# BMS029B_Monitor.net
KiCad netlist of a schematic drawn in Altium Designer
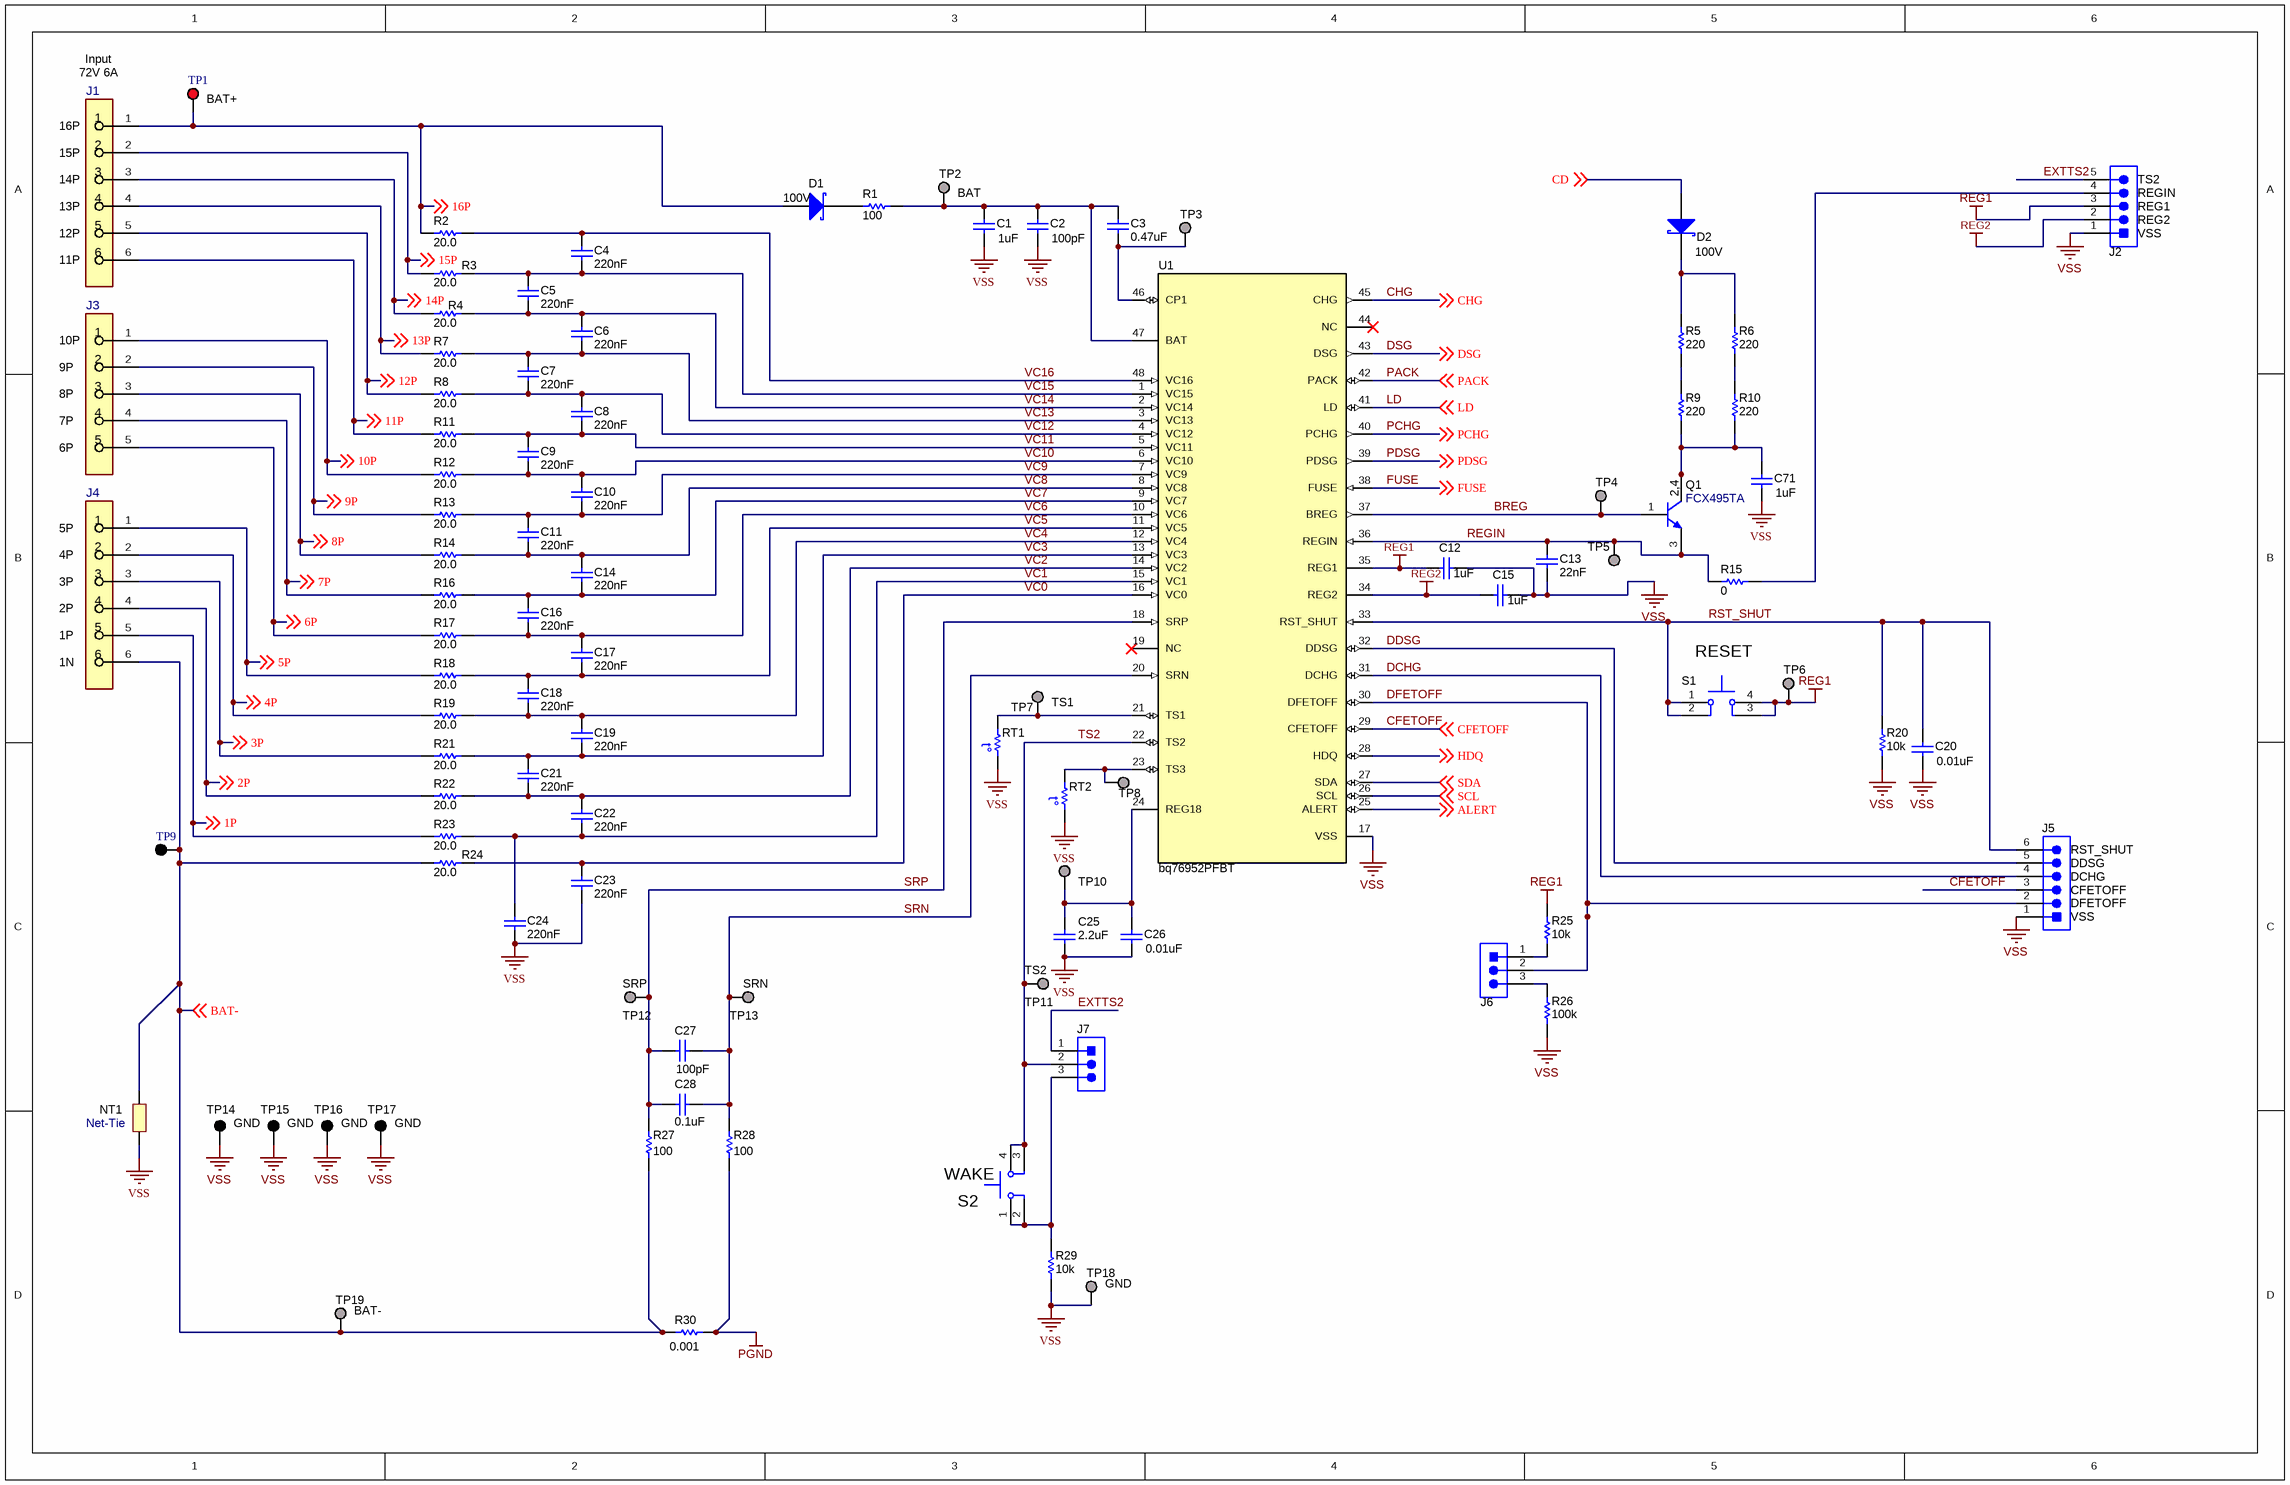
[diagram p0: BMS029B_Monitor.SchDoc]

(export (version "E")
  (design (tool "Eeschema 10.0.6"))
  (components
    (comp (ref "C1")
      (value "C3216X7R2A105K160AA")
      (footprint "1206_180")
      (description "CAP, CERM, 1 uF, 100 V, +/- 10%, X7R, 1206")
      (fields
        (field (name "MANUFACTURER") "TDK")
        (field (name "VALUEDISPLAYED") "1uF")
        (field (name "PUBLISHER") "Texas Instruments")
      )
      (libsource (lib "Altium Vault - TI") (part "Capacitor"))
    )
    (comp (ref "C2")
      (value "GCM1885C2A101JA16D")
      (footprint "0603")
      (description "CAP, CERM, 100 pF, 100 V, +/- 5%, C0G/NP0, AEC-Q200 Grade 1, 0603")
      (fields
        (field (name "MANUFACTURER") "MuRata")
        (field (name "VALUEDISPLAYED") "100pF")
        (field (name "PUBLISHER") "Texas Instruments")
      )
      (libsource (lib "Altium Vault - TI") (part "Capacitor"))
    )
    (comp (ref "C3")
      (value "GCM219R71E474KA55D")
      (footprint "0805_HV")
      (description "CAP, CERM, 0.47 uF, 25 V, +/- 10%, X7R, AEC-Q200 Grade 1, 0805")
      (fields
        (field (name "MANUFACTURER") "MuRata")
        (field (name "VALUEDISPLAYED") "0.47uF")
        (field (name "PUBLISHER") "Texas Instruments")
      )
      (libsource (lib "Altium Vault - TI") (part "Capacitor"))
    )
    (comp (ref "C4")
      (value "C1608X7R1H224K080AB")
      (footprint "0603S")
      (description "CAP, CERM, 0.22 uF, 50 V, +/- 10%, X7R, 0603")
      (fields
        (field (name "MANUFACTURER") "TDK")
        (field (name "CAP_F") "220nF")
        (field (name "PUBLISHER") "Texas Instruments")
      )
      (libsource (lib "Altium Vault - TI") (part "Capacitor"))
    )
    (comp (ref "C5")
      (value "C1608X7R1H224K080AB")
      (footprint "0603S")
      (description "CAP, CERM, 0.22 uF, 50 V, +/- 10%, X7R, 0603")
      (fields
        (field (name "MANUFACTURER") "TDK")
        (field (name "CAP_F") "220nF")
        (field (name "PUBLISHER") "Texas Instruments")
      )
      (libsource (lib "Altium Vault - TI") (part "Capacitor"))
    )
    (comp (ref "C6")
      (value "C1608X7R1H224K080AB")
      (footprint "0603S")
      (description "CAP, CERM, 0.22 uF, 50 V, +/- 10%, X7R, 0603")
      (fields
        (field (name "MANUFACTURER") "TDK")
        (field (name "CAP_F") "220nF")
        (field (name "PUBLISHER") "Texas Instruments")
      )
      (libsource (lib "Altium Vault - TI") (part "Capacitor"))
    )
    (comp (ref "C7")
      (value "C1608X7R1H224K080AB")
      (footprint "0603S")
      (description "CAP, CERM, 0.22 uF, 50 V, +/- 10%, X7R, 0603")
      (fields
        (field (name "MANUFACTURER") "TDK")
        (field (name "CAP_F") "220nF")
        (field (name "PUBLISHER") "Texas Instruments")
      )
      (libsource (lib "Altium Vault - TI") (part "Capacitor"))
    )
    (comp (ref "C8")
      (value "C1608X7R1H224K080AB")
      (footprint "0603S")
      (description "CAP, CERM, 0.22 uF, 50 V, +/- 10%, X7R, 0603")
      (fields
        (field (name "MANUFACTURER") "TDK")
        (field (name "CAP_F") "220nF")
        (field (name "PUBLISHER") "Texas Instruments")
      )
      (libsource (lib "Altium Vault - TI") (part "Capacitor"))
    )
    (comp (ref "C9")
      (value "C1608X7R1H224K080AB")
      (footprint "0603S")
      (description "CAP, CERM, 0.22 uF, 50 V, +/- 10%, X7R, 0603")
      (fields
        (field (name "MANUFACTURER") "TDK")
        (field (name "CAP_F") "220nF")
        (field (name "PUBLISHER") "Texas Instruments")
      )
      (libsource (lib "Altium Vault - TI") (part "Capacitor"))
    )
    (comp (ref "C10")
      (value "C1608X7R1H224K080AB")
      (footprint "0603S")
      (description "CAP, CERM, 0.22 uF, 50 V, +/- 10%, X7R, 0603")
      (fields
        (field (name "MANUFACTURER") "TDK")
        (field (name "CAP_F") "220nF")
        (field (name "PUBLISHER") "Texas Instruments")
      )
      (libsource (lib "Altium Vault - TI") (part "Capacitor"))
    )
    (comp (ref "C11")
      (value "C1608X7R1H224K080AB")
      (footprint "0603S")
      (description "CAP, CERM, 0.22 uF, 50 V, +/- 10%, X7R, 0603")
      (fields
        (field (name "MANUFACTURER") "TDK")
        (field (name "CAP_F") "220nF")
        (field (name "PUBLISHER") "Texas Instruments")
      )
      (libsource (lib "Altium Vault - TI") (part "Capacitor"))
    )
    (comp (ref "C12")
      (value "EMK212B7105KG-T")
      (footprint "0805_HV")
      (description "CAP, CERM, 1 uF, 16 V, +/- 10%, X7R, 0805")
      (fields
        (field (name "MANUFACTURER") "Taiyo Yuden")
        (field (name "VALUEDISPLAYED") "1uF")
        (field (name "PUBLISHER") "Texas Instruments")
      )
      (libsource (lib "Altium Vault - TI") (part "Capacitor"))
    )
    (comp (ref "C13")
      (value "C0603C223K4RACTU")
      (footprint "0603")
      (description "CAP, CERM, 0.022 uF, 16 V, +/- 10%, X7R, 0603")
      (fields
        (field (name "MANUFACTURER") "Kemet")
        (field (name "CAP_F") "22nF")
        (field (name "PUBLISHER") "Texas Instruments")
      )
      (libsource (lib "Altium Vault - TI") (part "Capacitor"))
    )
    (comp (ref "C14")
      (value "C1608X7R1H224K080AB")
      (footprint "0603S")
      (description "CAP, CERM, 0.22 uF, 50 V, +/- 10%, X7R, 0603")
      (fields
        (field (name "MANUFACTURER") "TDK")
        (field (name "CAP_F") "220nF")
        (field (name "PUBLISHER") "Texas Instruments")
      )
      (libsource (lib "Altium Vault - TI") (part "Capacitor"))
    )
    (comp (ref "C15")
      (value "EMK212B7105KG-T")
      (footprint "0805_HV")
      (description "CAP, CERM, 1 uF, 16 V, +/- 10%, X7R, 0805")
      (fields
        (field (name "MANUFACTURER") "Taiyo Yuden")
        (field (name "VALUEDISPLAYED") "1uF")
        (field (name "PUBLISHER") "Texas Instruments")
      )
      (libsource (lib "Altium Vault - TI") (part "Capacitor"))
    )
    (comp (ref "C16")
      (value "C1608X7R1H224K080AB")
      (footprint "0603S")
      (description "CAP, CERM, 0.22 uF, 50 V, +/- 10%, X7R, 0603")
      (fields
        (field (name "MANUFACTURER") "TDK")
        (field (name "CAP_F") "220nF")
        (field (name "PUBLISHER") "Texas Instruments")
      )
      (libsource (lib "Altium Vault - TI") (part "Capacitor"))
    )
    (comp (ref "C17")
      (value "C1608X7R1H224K080AB")
      (footprint "0603S")
      (description "CAP, CERM, 0.22 uF, 50 V, +/- 10%, X7R, 0603")
      (fields
        (field (name "MANUFACTURER") "TDK")
        (field (name "CAP_F") "220nF")
        (field (name "PUBLISHER") "Texas Instruments")
      )
      (libsource (lib "Altium Vault - TI") (part "Capacitor"))
    )
    (comp (ref "C18")
      (value "C1608X7R1H224K080AB")
      (footprint "0603S")
      (description "CAP, CERM, 0.22 uF, 50 V, +/- 10%, X7R, 0603")
      (fields
        (field (name "MANUFACTURER") "TDK")
        (field (name "CAP_F") "220nF")
        (field (name "PUBLISHER") "Texas Instruments")
      )
      (libsource (lib "Altium Vault - TI") (part "Capacitor"))
    )
    (comp (ref "C19")
      (value "C1608X7R1H224K080AB")
      (footprint "0603S")
      (description "CAP, CERM, 0.22 uF, 50 V, +/- 10%, X7R, 0603")
      (fields
        (field (name "MANUFACTURER") "TDK")
        (field (name "CAP_F") "220nF")
        (field (name "PUBLISHER") "Texas Instruments")
      )
      (libsource (lib "Altium Vault - TI") (part "Capacitor"))
    )
    (comp (ref "C20")
      (value "885012206040")
      (footprint "0603")
      (description "CAP, CERM, 0.01 uF, 16 V, +/- 10%, X7R, 0603")
      (fields
        (field (name "MANUFACTURER") "Wurth Elektronik")
        (field (name "VALUEDISPLAYED") "0.01uF")
        (field (name "PUBLISHER") "Texas Instruments")
      )
      (libsource (lib "Altium Vault - TI") (part "Capacitor"))
    )
    (comp (ref "C21")
      (value "C1608X7R1H224K080AB")
      (footprint "0603S")
      (description "CAP, CERM, 0.22 uF, 50 V, +/- 10%, X7R, 0603")
      (fields
        (field (name "MANUFACTURER") "TDK")
        (field (name "CAP_F") "220nF")
        (field (name "PUBLISHER") "Texas Instruments")
      )
      (libsource (lib "Altium Vault - TI") (part "Capacitor"))
    )
    (comp (ref "C22")
      (value "C1608X7R1H224K080AB")
      (footprint "0603S")
      (description "CAP, CERM, 0.22 uF, 50 V, +/- 10%, X7R, 0603")
      (fields
        (field (name "MANUFACTURER") "TDK")
        (field (name "CAP_F") "220nF")
        (field (name "PUBLISHER") "Texas Instruments")
      )
      (libsource (lib "Altium Vault - TI") (part "Capacitor"))
    )
    (comp (ref "C23")
      (value "C1608X7R1H224K080AB")
      (footprint "0603S")
      (description "CAP, CERM, 0.22 uF, 50 V, +/- 10%, X7R, 0603")
      (fields
        (field (name "MANUFACTURER") "TDK")
        (field (name "CAP_F") "220nF")
        (field (name "PUBLISHER") "Texas Instruments")
      )
      (libsource (lib "Altium Vault - TI") (part "Capacitor"))
    )
    (comp (ref "C24")
      (value "C1608X7R1H224K080AB")
      (footprint "0603S")
      (description "CAP, CERM, 0.22 uF, 50 V, +/- 10%, X7R, 0603")
      (fields
        (field (name "MANUFACTURER") "TDK")
        (field (name "CAP_F") "220nF")
        (field (name "PUBLISHER") "Texas Instruments")
      )
      (libsource (lib "Altium Vault - TI") (part "Capacitor"))
    )
    (comp (ref "C25")
      (value "EMK212B7225KG-T")
      (footprint "0805_HV")
      (description "CAP, CERM, 2.2 uF, 16 V, +/- 10%, X7R, 0805")
      (fields
        (field (name "MANUFACTURER") "Taiyo Yuden")
        (field (name "VALUEDISPLAYED") "2.2uF")
        (field (name "PUBLISHER") "Texas Instruments")
      )
      (libsource (lib "Altium Vault - TI") (part "Capacitor"))
    )
    (comp (ref "C26")
      (value "885012206040")
      (footprint "0603")
      (description "CAP, CERM, 0.01 uF, 16 V, +/- 10%, X7R, 0603")
      (fields
        (field (name "MANUFACTURER") "Wurth Elektronik")
        (field (name "VALUEDISPLAYED") "0.01uF")
        (field (name "PUBLISHER") "Texas Instruments")
      )
      (libsource (lib "Altium Vault - TI") (part "Capacitor"))
    )
    (comp (ref "C27")
      (value "C0603C101J5GACTU")
      (footprint "0603")
      (description "CAP, CERM, 100 pF, 50 V, +/- 5%, C0G/NP0, 0603")
      (fields
        (field (name "MANUFACTURER") "Kemet")
        (field (name "VALUEDISPLAYED") "100pF")
        (field (name "PUBLISHER") "Texas Instruments")
      )
      (libsource (lib "Altium Vault - TI") (part "Capacitor"))
    )
    (comp (ref "C28")
      (value "885012206095")
      (footprint "0603")
      (description "CAP, CERM, 0.1 uF, 50 V, +/- 10%, X7R, 0603")
      (fields
        (field (name "MANUFACTURER") "Wurth Elektronik")
        (field (name "VALUEDISPLAYED") "0.1uF")
        (field (name "PUBLISHER") "Texas Instruments")
      )
      (libsource (lib "Altium Vault - TI") (part "Capacitor"))
    )
    (comp (ref "C71")
      (value "C3216X7R2A105K160AA")
      (footprint "1206_180")
      (description "CAP, CERM, 1 uF, 100 V, +/- 10%, X7R, 1206")
      (fields
        (field (name "MANUFACTURER") "TDK")
        (field (name "VALUEDISPLAYED") "1uF")
        (field (name "PUBLISHER") "Texas Instruments")
      )
      (libsource (lib "Altium Vault - TI") (part "Capacitor"))
    )
    (comp (ref "D1")
      (value "100V")
      (footprint "SOD-123")
      (description "Diode, Schottky, 100 V, 0.15 A, SOD-123")
      (fields (field (name "MANUFACTURER") "Diodes Inc.") (field (name "PARTNUMBER") "BAT46W-7-F"))
      (libsource (lib "Altium Vault - TI") (part "DIODE_SCHOTTKY"))
    )
    (comp (ref "D2")
      (value "100V")
      (footprint "SOD-123")
      (description "Diode, Schottky, 100 V, 0.15 A, SOD-123")
      (fields (field (name "MANUFACTURER") "Diodes Inc.") (field (name "PARTNUMBER") "BAT46W-7-F"))
      (libsource (lib "Altium Vault - TI") (part "DIODE_SCHOTTKY"))
    )
    (comp (ref "J1")
      (value "OSTTE060161")
      (footprint "FP-OSTTE060161_HDR6-MFG")
      (description "TERM BLOCK 3.5MM VERT 6POS PCB")
      (fields (field (name "MANUFACTURER") "On Shore Technology"))
      (libsource (lib "Altium Vault - TI") (part "SYM-OSTTE060161"))
    )
    (comp (ref "J2")
      (value "PEC05SAAN")
      (footprint "Sullins_PxC05SAAN")
      (description "Header, 2.54mm, 5x1, Tin, TH")
      (fields
        (field (name "MANUFACTURER") "Sullins Connector Solutions")
        (field (name "PUBLISHER") "Texas Instruments")
      )
      (libsource (lib "Altium Vault - TI") (part "CMP-0054597-1"))
    )
    (comp (ref "J3")
      (value "OSTTE050161")
      (footprint "FP-OSTTE050161_HDR5-MFG")
      (description "TERM BLOCK 3.5MM VERT 5POS PCB")
      (fields (field (name "MANUFACTURER") "On Shore Technology"))
      (libsource (lib "Altium Vault - TI") (part "SYM-OSTTE050161"))
    )
    (comp (ref "J4")
      (value "OSTTE060161")
      (footprint "FP-OSTTE060161_HDR6-MFG")
      (description "TERM BLOCK 3.5MM VERT 6POS PCB")
      (fields (field (name "MANUFACTURER") "On Shore Technology"))
      (libsource (lib "Altium Vault - TI") (part "SYM-OSTTE060161"))
    )
    (comp (ref "J5")
      (value "PEC06SAAN")
      (footprint "Sullins_PEC06SAAN")
      (description "Header, 100mil, 6x1, Tin, TH")
      (fields
        (field (name "MANUFACTURER") "Sullins Connector Solutions")
        (field (name "PUBLISHER") "Texas Instruments")
      )
      (libsource (lib "Altium Vault - TI") (part "Header_6x1"))
    )
    (comp (ref "J6")
      (value "87898-0304")
      (footprint "Molex_87898-0304")
      (description "Header, 2.54mm, 3x1, Gold, SMT")
      (fields (field (name "MANUFACTURER") "Molex") (field (name "PUBLISHER") "Texas Instruments"))
      (libsource (lib "Altium Vault - TI") (part "CMP-0075388-1"))
    )
    (comp (ref "J7")
      (value "87898-0304")
      (footprint "Molex_87898-0304")
      (description "Header, 2.54mm, 3x1, Gold, SMT")
      (fields (field (name "MANUFACTURER") "Molex") (field (name "PUBLISHER") "Texas Instruments"))
      (libsource (lib "") (part "CMP-0075388-1_1"))
    )
    (comp (ref "NT1")
      (value "Net-Tie")
      (footprint "Net-Tie_10milWide_30milLong")
      (description "Single point connection between nets.")
      (libsource (lib "Altium Vault - TI") (part "Net-Tie"))
    )
    (comp (ref "Q1")
      (value "FCX495TA")
      (footprint "SOT-89-3")
      (description "Transistor, NPN, 150 V, 1 A, AEC-Q101, SOT-89")
      (fields (field (name "MANUFACTURER") "Diodes Inc.") (field (name "PUBLISHER") "Texas Instruments"))
      (libsource (lib "Altium Vault - TI") (part "BJT_NPN_C24B1E3"))
    )
    (comp (ref "R1")
      (value "Resistor")
      (footprint "0603")
      (description "RES, 100, 5%, 0.1 W, AEC-Q200 Grade 0, 0603")
      (fields
        (field (name "PARTNUMBER") "CRCW0603100RJNEA")
        (field (name "MANUFACTURER") "Vishay-Dale")
        (field (name "VALUEDISPLAYED") "100")
        (field (name "PUBLISHER") "Texas Instruments")
      )
      (libsource (lib "Altium Vault - TI") (part "Resistor"))
    )
    (comp (ref "R2")
      (value "CRCW120620R0FKEA")
      (footprint "1206")
      (description "RES, 20.0, 1%, 0.25 W, AEC-Q200 Grade 0, 1206")
      (fields (field (name "MANUFACTURER") "Vishay-Dale") (field (name "VALUEDISPLAYED") "20.0"))
      (libsource (lib "Altium Vault - TI") (part "CMP-0016781-3"))
    )
    (comp (ref "R3")
      (value "CRCW120620R0FKEA")
      (footprint "1206")
      (description "RES, 20.0, 1%, 0.25 W, AEC-Q200 Grade 0, 1206")
      (fields (field (name "MANUFACTURER") "Vishay-Dale") (field (name "VALUEDISPLAYED") "20.0"))
      (libsource (lib "Altium Vault - TI") (part "Resistor"))
    )
    (comp (ref "R4")
      (value "CRCW120620R0FKEA")
      (footprint "1206")
      (description "RES, 20.0, 1%, 0.25 W, AEC-Q200 Grade 0, 1206")
      (fields (field (name "MANUFACTURER") "Vishay-Dale") (field (name "VALUEDISPLAYED") "20.0"))
      (libsource (lib "Altium Vault - TI") (part "Resistor"))
    )
    (comp (ref "R5")
      (value "CRCW2512220RJNEG")
      (footprint "2512")
      (description "RES, 220, 5%, 1 W, AEC-Q200 Grade 0, 2512")
      (fields (field (name "MANUFACTURER") "Vishay-Dale") (field (name "VALUEDISPLAYED") "220"))
      (libsource (lib "Altium Vault - TI") (part "Resistor"))
    )
    (comp (ref "R6")
      (value "CRCW2512220RJNEG")
      (footprint "2512")
      (description "RES, 220, 5%, 1 W, AEC-Q200 Grade 0, 2512")
      (fields (field (name "MANUFACTURER") "Vishay-Dale") (field (name "VALUEDISPLAYED") "220"))
      (libsource (lib "Altium Vault - TI") (part "Resistor"))
    )
    (comp (ref "R7")
      (value "CRCW120620R0FKEA")
      (footprint "1206")
      (description "RES, 20.0, 1%, 0.25 W, AEC-Q200 Grade 0, 1206")
      (fields (field (name "MANUFACTURER") "Vishay-Dale") (field (name "VALUEDISPLAYED") "20.0"))
      (libsource (lib "Altium Vault - TI") (part "Resistor"))
    )
    (comp (ref "R8")
      (value "CRCW120620R0FKEA")
      (footprint "1206")
      (description "RES, 20.0, 1%, 0.25 W, AEC-Q200 Grade 0, 1206")
      (fields (field (name "MANUFACTURER") "Vishay-Dale") (field (name "VALUEDISPLAYED") "20.0"))
      (libsource (lib "Altium Vault - TI") (part "Resistor"))
    )
    (comp (ref "R9")
      (value "CRCW2512220RJNEG")
      (footprint "2512")
      (description "RES, 220, 5%, 1 W, AEC-Q200 Grade 0, 2512")
      (fields (field (name "MANUFACTURER") "Vishay-Dale") (field (name "VALUEDISPLAYED") "220"))
      (libsource (lib "Altium Vault - TI") (part "Resistor"))
    )
    (comp (ref "R10")
      (value "CRCW2512220RJNEG")
      (footprint "2512")
      (description "RES, 220, 5%, 1 W, AEC-Q200 Grade 0, 2512")
      (fields (field (name "MANUFACTURER") "Vishay-Dale") (field (name "VALUEDISPLAYED") "220"))
      (libsource (lib "Altium Vault - TI") (part "Resistor"))
    )
    (comp (ref "R11")
      (value "CRCW120620R0FKEA")
      (footprint "1206")
      (description "RES, 20.0, 1%, 0.25 W, AEC-Q200 Grade 0, 1206")
      (fields (field (name "MANUFACTURER") "Vishay-Dale") (field (name "VALUEDISPLAYED") "20.0"))
      (libsource (lib "Altium Vault - TI") (part "Resistor"))
    )
    (comp (ref "R12")
      (value "CRCW120620R0FKEA")
      (footprint "1206")
      (description "RES, 20.0, 1%, 0.25 W, AEC-Q200 Grade 0, 1206")
      (fields (field (name "MANUFACTURER") "Vishay-Dale") (field (name "VALUEDISPLAYED") "20.0"))
      (libsource (lib "Altium Vault - TI") (part "Resistor"))
    )
    (comp (ref "R13")
      (value "CRCW120620R0FKEA")
      (footprint "1206")
      (description "RES, 20.0, 1%, 0.25 W, AEC-Q200 Grade 0, 1206")
      (fields (field (name "MANUFACTURER") "Vishay-Dale") (field (name "VALUEDISPLAYED") "20.0"))
      (libsource (lib "Altium Vault - TI") (part "Resistor"))
    )
    (comp (ref "R14")
      (value "CRCW120620R0FKEA")
      (footprint "1206")
      (description "RES, 20.0, 1%, 0.25 W, AEC-Q200 Grade 0, 1206")
      (fields (field (name "MANUFACTURER") "Vishay-Dale") (field (name "VALUEDISPLAYED") "20.0"))
      (libsource (lib "Altium Vault - TI") (part "CMP-0016781-3"))
    )
    (comp (ref "R15")
      (value "CRCW06030000Z0EA")
      (footprint "0603")
      (description "RES, 0, 5%, 0.1 W, AEC-Q200 Grade 0, 0603")
      (fields (field (name "MANUFACTURER") "Vishay-Dale") (field (name "VALUEDISPLAYED") "0"))
      (libsource (lib "Altium Vault - TI") (part "Resistor"))
    )
    (comp (ref "R16")
      (value "CRCW120620R0FKEA")
      (footprint "1206")
      (description "RES, 20.0, 1%, 0.25 W, AEC-Q200 Grade 0, 1206")
      (fields (field (name "MANUFACTURER") "Vishay-Dale") (field (name "VALUEDISPLAYED") "20.0"))
      (libsource (lib "Altium Vault - TI") (part "Resistor"))
    )
    (comp (ref "R17")
      (value "CRCW120620R0FKEA")
      (footprint "1206")
      (description "RES, 20.0, 1%, 0.25 W, AEC-Q200 Grade 0, 1206")
      (fields (field (name "MANUFACTURER") "Vishay-Dale") (field (name "VALUEDISPLAYED") "20.0"))
      (libsource (lib "Altium Vault - TI") (part "Resistor"))
    )
    (comp (ref "R18")
      (value "CRCW120620R0FKEA")
      (footprint "1206")
      (description "RES, 20.0, 1%, 0.25 W, AEC-Q200 Grade 0, 1206")
      (fields (field (name "MANUFACTURER") "Vishay-Dale") (field (name "VALUEDISPLAYED") "20.0"))
      (libsource (lib "Altium Vault - TI") (part "Resistor"))
    )
    (comp (ref "R19")
      (value "CRCW120620R0FKEA")
      (footprint "1206")
      (description "RES, 20.0, 1%, 0.25 W, AEC-Q200 Grade 0, 1206")
      (fields (field (name "MANUFACTURER") "Vishay-Dale") (field (name "VALUEDISPLAYED") "20.0"))
      (libsource (lib "Altium Vault - TI") (part "Resistor"))
    )
    (comp (ref "R20")
      (value "CRCW060310K0JNEA")
      (footprint "0603")
      (description "RES, 10 k, 5%, 0.1 W, AEC-Q200 Grade 0, 0603")
      (fields (field (name "MANUFACTURER") "Vishay-Dale") (field (name "VALUEDISPLAYED") "10k"))
      (libsource (lib "Altium Vault - TI") (part "Resistor"))
    )
    (comp (ref "R21")
      (value "CRCW120620R0FKEA")
      (footprint "1206")
      (description "RES, 20.0, 1%, 0.25 W, AEC-Q200 Grade 0, 1206")
      (fields (field (name "MANUFACTURER") "Vishay-Dale") (field (name "VALUEDISPLAYED") "20.0"))
      (libsource (lib "Altium Vault - TI") (part "Resistor"))
    )
    (comp (ref "R22")
      (value "CRCW120620R0FKEA")
      (footprint "1206")
      (description "RES, 20.0, 1%, 0.25 W, AEC-Q200 Grade 0, 1206")
      (fields (field (name "MANUFACTURER") "Vishay-Dale") (field (name "VALUEDISPLAYED") "20.0"))
      (libsource (lib "Altium Vault - TI") (part "Resistor"))
    )
    (comp (ref "R23")
      (value "CRCW120620R0FKEA")
      (footprint "1206")
      (description "RES, 20.0, 1%, 0.25 W, AEC-Q200 Grade 0, 1206")
      (fields (field (name "MANUFACTURER") "Vishay-Dale") (field (name "VALUEDISPLAYED") "20.0"))
      (libsource (lib "Altium Vault - TI") (part "Resistor"))
    )
    (comp (ref "R24")
      (value "CRCW120620R0FKEA")
      (footprint "1206")
      (description "RES, 20.0, 1%, 0.25 W, AEC-Q200 Grade 0, 1206")
      (fields (field (name "MANUFACTURER") "Vishay-Dale") (field (name "VALUEDISPLAYED") "20.0"))
      (libsource (lib "Altium Vault - TI") (part "Resistor"))
    )
    (comp (ref "R25")
      (value "CRCW060310K0JNEA")
      (footprint "0603")
      (description "RES, 10 k, 5%, 0.1 W, AEC-Q200 Grade 0, 0603")
      (fields (field (name "MANUFACTURER") "Vishay-Dale") (field (name "VALUEDISPLAYED") "10k"))
      (libsource (lib "Altium Vault - TI") (part "Resistor"))
    )
    (comp (ref "R26")
      (value "CRCW0603100KJNEA")
      (footprint "0603")
      (description "RES, 100 k, 5%, 0.1 W, AEC-Q200 Grade 0, 0603")
      (fields (field (name "MANUFACTURER") "Vishay-Dale") (field (name "VALUEDISPLAYED") "100k"))
      (libsource (lib "Altium Vault - TI") (part "Resistor"))
    )
    (comp (ref "R27")
      (value "Resistor")
      (footprint "0603")
      (description "RES, 100, 5%, 0.1 W, AEC-Q200 Grade 0, 0603")
      (fields
        (field (name "PARTNUMBER") "CRCW0603100RJNEA")
        (field (name "MANUFACTURER") "Vishay-Dale")
        (field (name "VALUEDISPLAYED") "100")
        (field (name "PUBLISHER") "Texas Instruments")
      )
      (libsource (lib "Altium Vault - TI") (part "Resistor"))
    )
    (comp (ref "R28")
      (value "Resistor")
      (footprint "0603")
      (description "RES, 100, 5%, 0.1 W, AEC-Q200 Grade 0, 0603")
      (fields
        (field (name "PARTNUMBER") "CRCW0603100RJNEA")
        (field (name "MANUFACTURER") "Vishay-Dale")
        (field (name "VALUEDISPLAYED") "100")
        (field (name "PUBLISHER") "Texas Instruments")
      )
      (libsource (lib "Altium Vault - TI") (part "Resistor"))
    )
    (comp (ref "R29")
      (value "CRCW060310K0JNEA")
      (footprint "0603")
      (description "RES, 10 k, 5%, 0.1 W, AEC-Q200 Grade 0, 0603")
      (fields (field (name "MANUFACTURER") "Vishay-Dale") (field (name "VALUEDISPLAYED") "10k"))
      (libsource (lib "Altium Vault - TI") (part "Resistor"))
    )
    (comp (ref "R30")
      (value "Resistor")
      (footprint "1210M")
      (description "RES, 0.001, 1%, 1 W, 1210")
      (fields
        (field (name "PARTNUMBER") "PMR25HZPFV1L00")
        (field (name "MANUFACTURER") "Rohm")
        (field (name "VALUEDISPLAYED") "0.001")
        (field (name "PUBLISHER") "Texas Instruments")
      )
      (libsource (lib "Altium Vault - TI") (part "Resistor"))
    )
    (comp (ref "RT1")
      (value "Thermistor")
      (footprint "THERMISTOR_103AT-2")
      (description "Thermistor NTC, 10.0k ohm, 1%, Disc, 5x8.4 mm")
      (fields
        (field (name "PARTNUMBER") "103AT-2")
        (field (name "MANUFACTURER") "SEMITEC Corporation")
        (field (name "PUBLISHER") "Texas Instruments")
      )
      (libsource (lib "Altium Vault - TI") (part "Thermistor"))
    )
    (comp (ref "RT2")
      (value "Thermistor")
      (footprint "THERMISTOR_103AT-2")
      (description "Thermistor NTC, 10.0k ohm, 1%, Disc, 5x8.4 mm")
      (fields
        (field (name "PARTNUMBER") "103AT-2")
        (field (name "MANUFACTURER") "SEMITEC Corporation")
        (field (name "PUBLISHER") "Texas Instruments")
      )
      (libsource (lib "Altium Vault - TI") (part "Thermistor"))
    )
    (comp (ref "S1")
      (value "SW_KST221JLFS")
      (footprint "SW_KST221JLFS")
      (description "Switch, Tactile, SPST-NO, SMT")
      (fields
        (field (name "PARTNUMBER") "KST221JLFS")
        (field (name "MANUFACTURER") "C&K Components")
        (field (name "SYMBOLCREATOR") "a0799628")
        (field (name "PUBLISHER") "Texas Instruments")
      )
      (libsource (lib "Altium Vault - TI") (part "SW_KST221JLFS"))
    )
    (comp (ref "S2")
      (value "SW_KST221JLFS")
      (footprint "SW_KST221JLFS")
      (description "Switch, Tactile, SPST-NO, SMT")
      (fields
        (field (name "PARTNUMBER") "KST221JLFS")
        (field (name "MANUFACTURER") "C&K Components")
        (field (name "SYMBOLCREATOR") "a0799628")
        (field (name "PUBLISHER") "Texas Instruments")
      )
      (libsource (lib "Altium Vault - TI") (part "SW_KST221JLFS"))
    )
    (comp (ref "TP1")
      (value "TESTPOINT")
      (footprint "Keystone5010")
      (description "Test Point, Multipurpose, Red, TH")
      (fields
        (field (name "MANUFACTURER") "Keystone")
        (field (name "PARTNUMBER") "5010")
        (field (name "PUBLISHER") "Texas Instruments")
      )
      (libsource (lib "Altium Vault - TI") (part "5010"))
    )
    (comp (ref "TP2")
      (value "TESTPOINT")
      (footprint "TP_VIA_060RND040")
      (description "TEST POINT.  No entry in BOM.")
      (libsource (lib "Altium Vault - TI") (part "TESTPOINT"))
    )
    (comp (ref "TP3")
      (value "TESTPOINT")
      (footprint "TP_VIA_060RND040")
      (description "TEST POINT.  No entry in BOM.")
      (libsource (lib "Altium Vault - TI") (part "CMP-0078143-2"))
    )
    (comp (ref "TP4")
      (value "TESTPOINT")
      (footprint "TP_VIA_060RND040")
      (description "TEST POINT.  No entry in BOM.")
      (libsource (lib "Altium Vault - TI") (part "CMP-0078143-2"))
    )
    (comp (ref "TP5")
      (value "TESTPOINT")
      (footprint "TP_VIA_060RND040")
      (description "TEST POINT.  No entry in BOM.")
      (libsource (lib "Altium Vault - TI") (part "CMP-0078143-2"))
    )
    (comp (ref "TP6")
      (value "TESTPOINT")
      (footprint "TP_VIA_060RND040")
      (description "TEST POINT.  No entry in BOM.")
      (libsource (lib "Altium Vault - TI") (part "CMP-0078143-2"))
    )
    (comp (ref "TP7")
      (value "TESTPOINT")
      (footprint "TP_VIA_060RND040")
      (description "TEST POINT.  No entry in BOM.")
      (libsource (lib "Altium Vault - TI") (part "CMP-0078143-2"))
    )
    (comp (ref "TP8")
      (value "TESTPOINT")
      (footprint "TP_VIA_060RND040")
      (description "TEST POINT.  No entry in BOM.")
      (libsource (lib "Altium Vault - TI") (part "CMP-0078143-2"))
    )
    (comp (ref "TP9")
      (value "TESTPOINT")
      (footprint "Keystone5011")
      (description "Test Point, Multipurpose, Black, TH")
      (fields
        (field (name "MANUFACTURER") "Keystone")
        (field (name "PARTNUMBER") "5011")
        (field (name "PUBLISHER") "Texas Instruments")
      )
      (libsource (lib "Altium Vault - TI") (part "5011"))
    )
    (comp (ref "TP10")
      (value "TESTPOINT")
      (footprint "TP_50MIL-25MILHOLE")
      (description "TEST POINT.  No entry in BOM.")
      (libsource (lib "Altium Vault - TI") (part "CMP-0078143-2"))
    )
    (comp (ref "TP11")
      (value "TESTPOINT")
      (footprint "TP_50MIL-25MILHOLE")
      (description "TEST POINT.  No entry in BOM.")
      (libsource (lib "Altium Vault - TI") (part "CMP-0078143-2"))
    )
    (comp (ref "TP12")
      (value "TESTPOINT")
      (footprint "TP_50MIL-25MILHOLE")
      (description "TEST POINT.  No entry in BOM.")
      (libsource (lib "Altium Vault - TI") (part "CMP-0078143-2"))
    )
    (comp (ref "TP13")
      (value "TESTPOINT")
      (footprint "TP_50MIL-25MILHOLE")
      (description "TEST POINT.  No entry in BOM.")
      (libsource (lib "Altium Vault - TI") (part "CMP-0078143-2"))
    )
    (comp (ref "TP14")
      (value "5006")
      (footprint "Keystone5006")
      (description "Test Point, Compact, Black, TH")
      (fields (field (name "MANUFACTURER") "Keystone") (field (name "PUBLISHER") "Texas Instruments"))
      (libsource (lib "Altium Vault - TI") (part "5006"))
    )
    (comp (ref "TP15")
      (value "5006")
      (footprint "Keystone5006")
      (description "Test Point, Compact, Black, TH")
      (fields (field (name "MANUFACTURER") "Keystone") (field (name "PUBLISHER") "Texas Instruments"))
      (libsource (lib "Altium Vault - TI") (part "5006"))
    )
    (comp (ref "TP16")
      (value "5006")
      (footprint "Keystone5006")
      (description "Test Point, Compact, Black, TH")
      (fields (field (name "MANUFACTURER") "Keystone") (field (name "PUBLISHER") "Texas Instruments"))
      (libsource (lib "Altium Vault - TI") (part "5006"))
    )
    (comp (ref "TP17")
      (value "5006")
      (footprint "Keystone5006")
      (description "Test Point, Compact, Black, TH")
      (fields (field (name "MANUFACTURER") "Keystone") (field (name "PUBLISHER") "Texas Instruments"))
      (libsource (lib "Altium Vault - TI") (part "5006"))
    )
    (comp (ref "TP18")
      (value "TESTPOINT")
      (footprint "TP_VIA_060RND040")
      (description "TEST POINT.  No entry in BOM.")
      (libsource (lib "Altium Vault - TI") (part "TESTPOINT"))
    )
    (comp (ref "TP19")
      (value "TESTPOINT")
      (footprint "TP_VIA_060RND040")
      (description "TEST POINT.  No entry in BOM.")
      (libsource (lib "Altium Vault - TI") (part "TESTPOINT"))
    )
    (comp (ref "U1")
      (value "bq76952PFBT")
      (footprint "PFB0048A_N")
      (description "Multicell Battery Monitor and Protection Family, PFB0048A (TQFP-48)")
      (fields
        (field (name "ALTERNATE PARTNUMBER") "bq76952PFBR")
        (field (name "MANUFACTURER") "Texas Instruments")
        (field (name "PARTNUMBER") "bq76952PFBT")
      )
      (libsource (lib "Altium Vault - TI") (part "bq76952"))
    )
  )
  (nets
    (net (code "1") (name "/BREG") (class "Default")
      (node (ref "Q1") (pin "1") (pinfunction "B_1") (pintype "passive"))
      (node (ref "TP4") (pin "1") (pintype "passive"))
      (node (ref "U1") (pin "37") (pinfunction "BREG_37") (pintype "output"))
    )
    (net (code "2") (name "/DCHG") (class "Default")
      (node (ref "J5") (pin "4") (pinfunction "4_4") (pintype "passive"))
      (node (ref "U1") (pin "31") (pinfunction "DCHG_31") (pintype "bidirectional"))
    )
    (net (code "3") (name "/DDSG") (class "Default")
      (node (ref "J5") (pin "5") (pinfunction "5_5") (pintype "passive"))
      (node (ref "U1") (pin "32") (pinfunction "DDSG_32") (pintype "bidirectional"))
    )
    (net (code "4") (name "/DFETOFF") (class "Default")
      (node (ref "J5") (pin "2") (pinfunction "2_2") (pintype "passive"))
      (node (ref "J6") (pin "2") (pinfunction "2_2") (pintype "passive"))
      (node (ref "U1") (pin "30") (pinfunction "DFETOFF_30") (pintype "bidirectional"))
    )
    (net (code "5") (name "/EXTTS2") (class "Default")
      (node (ref "J2") (pin "5") (pinfunction "5_5") (pintype "passive"))
      (node (ref "J7") (pin "1") (pinfunction "1_1") (pintype "passive"))
    )
    (net (code "6") (name "/REGIN") (class "Default")
      (node (ref "C13") (pin "2") (pinfunction "2_2") (pintype "passive"))
      (node (ref "Q1") (pin "3") (pinfunction "E_3") (pintype "passive"))
      (node (ref "R15") (pin "1") (pinfunction "1_1") (pintype "passive"))
      (node (ref "TP5") (pin "1") (pintype "passive"))
      (node (ref "U1") (pin "36") (pinfunction "REGIN_36") (pintype "input"))
    )
    (net (code "7") (name "/RST_SHUT") (class "Default")
      (node (ref "C20") (pin "1") (pinfunction "1_1") (pintype "passive"))
      (node (ref "J5") (pin "6") (pinfunction "6_6") (pintype "passive"))
      (node (ref "R20") (pin "1") (pinfunction "1_1") (pintype "passive"))
      (node (ref "S1") (pin "1") (pinfunction "1_1") (pintype "passive"))
      (node (ref "S1") (pin "2") (pinfunction "2_2") (pintype "passive"))
      (node (ref "U1") (pin "33") (pinfunction "RST_SHUT_33") (pintype "input"))
    )
    (net (code "8") (name "/SRN") (class "Default")
      (node (ref "C27") (pin "1") (pinfunction "1_1") (pintype "passive"))
      (node (ref "C28") (pin "2") (pinfunction "2_2") (pintype "passive"))
      (node (ref "R28") (pin "2") (pinfunction "2_2") (pintype "passive"))
      (node (ref "TP13") (pin "1") (pintype "passive"))
      (node (ref "U1") (pin "20") (pinfunction "SRN_20") (pintype "input"))
    )
    (net (code "9") (name "/SRP") (class "Default")
      (node (ref "C27") (pin "2") (pinfunction "2_2") (pintype "passive"))
      (node (ref "C28") (pin "1") (pinfunction "1_1") (pintype "passive"))
      (node (ref "R27") (pin "2") (pinfunction "2_2") (pintype "passive"))
      (node (ref "TP12") (pin "1") (pintype "passive"))
      (node (ref "U1") (pin "18") (pinfunction "SRP_18") (pintype "input"))
    )
    (net (code "10") (name "/TS2") (class "Default")
      (node (ref "J7") (pin "2") (pinfunction "2_2") (pintype "passive"))
      (node (ref "S2") (pin "3") (pinfunction "3_3") (pintype "passive"))
      (node (ref "S2") (pin "4") (pinfunction "4_4") (pintype "passive"))
      (node (ref "TP11") (pin "1") (pintype "passive"))
      (node (ref "U1") (pin "22") (pinfunction "TS2_22") (pintype "bidirectional"))
    )
    (net (code "11") (name "/VC0") (class "Default")
      (node (ref "C23") (pin "1") (pinfunction "1_1") (pintype "passive"))
      (node (ref "R24") (pin "2") (pinfunction "2_2") (pintype "passive"))
      (node (ref "U1") (pin "16") (pinfunction "VC0_16") (pintype "input"))
    )
    (net (code "12") (name "/VC1") (class "Default")
      (node (ref "C22") (pin "2") (pinfunction "2_2") (pintype "passive"))
      (node (ref "C24") (pin "1") (pinfunction "1_1") (pintype "passive"))
      (node (ref "R23") (pin "2") (pinfunction "2_2") (pintype "passive"))
      (node (ref "U1") (pin "15") (pinfunction "VC1_15") (pintype "input"))
    )
    (net (code "13") (name "/VC2") (class "Default")
      (node (ref "C21") (pin "2") (pinfunction "2_2") (pintype "passive"))
      (node (ref "C22") (pin "1") (pinfunction "1_1") (pintype "passive"))
      (node (ref "R22") (pin "2") (pinfunction "2_2") (pintype "passive"))
      (node (ref "U1") (pin "14") (pinfunction "VC2_14") (pintype "input"))
    )
    (net (code "14") (name "/VC3") (class "Default")
      (node (ref "C19") (pin "2") (pinfunction "2_2") (pintype "passive"))
      (node (ref "C21") (pin "1") (pinfunction "1_1") (pintype "passive"))
      (node (ref "R21") (pin "2") (pinfunction "2_2") (pintype "passive"))
      (node (ref "U1") (pin "13") (pinfunction "VC3_13") (pintype "input"))
    )
    (net (code "15") (name "/VC4") (class "Default")
      (node (ref "C18") (pin "2") (pinfunction "2_2") (pintype "passive"))
      (node (ref "C19") (pin "1") (pinfunction "1_1") (pintype "passive"))
      (node (ref "R19") (pin "2") (pinfunction "2_2") (pintype "passive"))
      (node (ref "U1") (pin "12") (pinfunction "VC4_12") (pintype "input"))
    )
    (net (code "16") (name "/VC5") (class "Default")
      (node (ref "C17") (pin "2") (pinfunction "2_2") (pintype "passive"))
      (node (ref "C18") (pin "1") (pinfunction "1_1") (pintype "passive"))
      (node (ref "R18") (pin "2") (pinfunction "2_2") (pintype "passive"))
      (node (ref "U1") (pin "11") (pinfunction "VC5_11") (pintype "input"))
    )
    (net (code "17") (name "/VC6") (class "Default")
      (node (ref "C16") (pin "2") (pinfunction "2_2") (pintype "passive"))
      (node (ref "C17") (pin "1") (pinfunction "1_1") (pintype "passive"))
      (node (ref "R17") (pin "2") (pinfunction "2_2") (pintype "passive"))
      (node (ref "U1") (pin "10") (pinfunction "VC6_10") (pintype "input"))
    )
    (net (code "18") (name "/VC7") (class "Default")
      (node (ref "C14") (pin "2") (pinfunction "2_2") (pintype "passive"))
      (node (ref "C16") (pin "1") (pinfunction "1_1") (pintype "passive"))
      (node (ref "R16") (pin "2") (pinfunction "2_2") (pintype "passive"))
      (node (ref "U1") (pin "9") (pinfunction "VC7_9") (pintype "input"))
    )
    (net (code "19") (name "/VC8") (class "Default")
      (node (ref "C11") (pin "2") (pinfunction "2_2") (pintype "passive"))
      (node (ref "C14") (pin "1") (pinfunction "1_1") (pintype "passive"))
      (node (ref "R14") (pin "2") (pinfunction "2_2") (pintype "passive"))
      (node (ref "U1") (pin "8") (pinfunction "VC8_8") (pintype "input"))
    )
    (net (code "20") (name "/VC9") (class "Default")
      (node (ref "C10") (pin "2") (pinfunction "2_2") (pintype "passive"))
      (node (ref "C11") (pin "1") (pinfunction "1_1") (pintype "passive"))
      (node (ref "R13") (pin "2") (pinfunction "2_2") (pintype "passive"))
      (node (ref "U1") (pin "7") (pinfunction "VC9_7") (pintype "input"))
    )
    (net (code "21") (name "/VC10") (class "Default")
      (node (ref "C10") (pin "1") (pinfunction "1_1") (pintype "passive"))
      (node (ref "C9") (pin "2") (pinfunction "2_2") (pintype "passive"))
      (node (ref "R12") (pin "2") (pinfunction "2_2") (pintype "passive"))
      (node (ref "U1") (pin "6") (pinfunction "VC10_6") (pintype "input"))
    )
    (net (code "22") (name "/VC11") (class "Default")
      (node (ref "C8") (pin "2") (pinfunction "2_2") (pintype "passive"))
      (node (ref "C9") (pin "1") (pinfunction "1_1") (pintype "passive"))
      (node (ref "R11") (pin "2") (pinfunction "2_2") (pintype "passive"))
      (node (ref "U1") (pin "5") (pinfunction "VC11_5") (pintype "input"))
    )
    (net (code "23") (name "/VC12") (class "Default")
      (node (ref "C7") (pin "2") (pinfunction "2_2") (pintype "passive"))
      (node (ref "C8") (pin "1") (pinfunction "1_1") (pintype "passive"))
      (node (ref "R8") (pin "2") (pinfunction "2_2") (pintype "passive"))
      (node (ref "U1") (pin "4") (pinfunction "VC12_4") (pintype "input"))
    )
    (net (code "24") (name "/VC13") (class "Default")
      (node (ref "C6") (pin "2") (pinfunction "2_2") (pintype "passive"))
      (node (ref "C7") (pin "1") (pinfunction "1_1") (pintype "passive"))
      (node (ref "R7") (pin "2") (pinfunction "2_2") (pintype "passive"))
      (node (ref "U1") (pin "3") (pinfunction "VC13_3") (pintype "input"))
    )
    (net (code "25") (name "/VC14") (class "Default")
      (node (ref "C5") (pin "2") (pinfunction "2_2") (pintype "passive"))
      (node (ref "C6") (pin "1") (pinfunction "1_1") (pintype "passive"))
      (node (ref "R4") (pin "2") (pinfunction "2_2") (pintype "passive"))
      (node (ref "U1") (pin "2") (pinfunction "VC14_2") (pintype "input"))
    )
    (net (code "26") (name "/VC15") (class "Default")
      (node (ref "C4") (pin "2") (pinfunction "2_2") (pintype "passive"))
      (node (ref "C5") (pin "1") (pinfunction "1_1") (pintype "passive"))
      (node (ref "R3") (pin "2") (pinfunction "2_2") (pintype "passive"))
      (node (ref "U1") (pin "1") (pinfunction "VC15_1") (pintype "input"))
    )
    (net (code "27") (name "/VC16") (class "Default")
      (node (ref "C4") (pin "1") (pinfunction "1_1") (pintype "passive"))
      (node (ref "R2") (pin "2") (pinfunction "2_2") (pintype "passive"))
      (node (ref "U1") (pin "48") (pinfunction "VC16_48") (pintype "input"))
    )
    (net (code "28") (name "1P") (class "Default")
      (node (ref "J4") (pin "5") (pinfunction "5_5") (pintype "passive"))
      (node (ref "R23") (pin "1") (pinfunction "1_1") (pintype "passive"))
    )
    (net (code "29") (name "2P") (class "Default")
      (node (ref "J4") (pin "4") (pinfunction "4_4") (pintype "passive"))
      (node (ref "R22") (pin "1") (pinfunction "1_1") (pintype "passive"))
    )
    (net (code "30") (name "3P") (class "Default")
      (node (ref "J4") (pin "3") (pinfunction "3_3") (pintype "passive"))
      (node (ref "R21") (pin "1") (pinfunction "1_1") (pintype "passive"))
    )
    (net (code "31") (name "4P") (class "Default")
      (node (ref "J4") (pin "2") (pinfunction "2_2") (pintype "passive"))
      (node (ref "R19") (pin "1") (pinfunction "1_1") (pintype "passive"))
    )
    (net (code "32") (name "5P") (class "Default")
      (node (ref "J4") (pin "1") (pinfunction "1_1") (pintype "passive"))
      (node (ref "R18") (pin "1") (pinfunction "1_1") (pintype "passive"))
    )
    (net (code "33") (name "6P") (class "Default")
      (node (ref "J3") (pin "5") (pinfunction "5_5") (pintype "passive"))
      (node (ref "R17") (pin "1") (pinfunction "1_1") (pintype "passive"))
    )
    (net (code "34") (name "7P") (class "Default")
      (node (ref "J3") (pin "4") (pinfunction "4_4") (pintype "passive"))
      (node (ref "R16") (pin "1") (pinfunction "1_1") (pintype "passive"))
    )
    (net (code "35") (name "8P") (class "Default")
      (node (ref "J3") (pin "3") (pinfunction "3_3") (pintype "passive"))
      (node (ref "R14") (pin "1") (pinfunction "1_1") (pintype "passive"))
    )
    (net (code "36") (name "9P") (class "Default")
      (node (ref "J3") (pin "2") (pinfunction "2_2") (pintype "passive"))
      (node (ref "R13") (pin "1") (pinfunction "1_1") (pintype "passive"))
    )
    (net (code "37") (name "10P") (class "Default")
      (node (ref "J3") (pin "1") (pinfunction "1_1") (pintype "passive"))
      (node (ref "R12") (pin "1") (pinfunction "1_1") (pintype "passive"))
    )
    (net (code "38") (name "11P") (class "Default")
      (node (ref "J1") (pin "6") (pinfunction "6_6") (pintype "passive"))
      (node (ref "R11") (pin "1") (pinfunction "1_1") (pintype "passive"))
    )
    (net (code "39") (name "12P") (class "Default")
      (node (ref "J1") (pin "5") (pinfunction "5_5") (pintype "passive"))
      (node (ref "R8") (pin "1") (pinfunction "1_1") (pintype "passive"))
    )
    (net (code "40") (name "13P") (class "Default")
      (node (ref "J1") (pin "4") (pinfunction "4_4") (pintype "passive"))
      (node (ref "R7") (pin "1") (pinfunction "1_1") (pintype "passive"))
    )
    (net (code "41") (name "14P") (class "Default")
      (node (ref "J1") (pin "3") (pinfunction "3_3") (pintype "passive"))
      (node (ref "R4") (pin "1") (pinfunction "1_1") (pintype "passive"))
    )
    (net (code "42") (name "15P") (class "Default")
      (node (ref "J1") (pin "2") (pinfunction "2_2") (pintype "passive"))
      (node (ref "R3") (pin "1") (pinfunction "1_1") (pintype "passive"))
    )
    (net (code "43") (name "16P") (class "Default")
      (node (ref "D1") (pin "2") (pinfunction "A_2") (pintype "passive"))
      (node (ref "J1") (pin "1") (pinfunction "1_1") (pintype "passive"))
      (node (ref "R2") (pin "1") (pinfunction "1_1") (pintype "passive"))
      (node (ref "TP1") (pin "1") (pintype "passive"))
    )
    (net (code "44") (name "ALERT") (class "Default")
      (node (ref "U1") (pin "25") (pinfunction "ALERT_25") (pintype "bidirectional"))
    )
    (net (code "45") (name "BAT-") (class "Default")
      (node (ref "J4") (pin "6") (pinfunction "6_6") (pintype "passive"))
      (node (ref "NT1") (pin "2") (pinfunction "2_2") (pintype "passive"))
      (node (ref "R24") (pin "1") (pinfunction "1_1") (pintype "passive"))
      (node (ref "R27") (pin "1") (pinfunction "1_1") (pintype "passive"))
      (node (ref "R30") (pin "2") (pinfunction "2_2") (pintype "passive"))
      (node (ref "TP19") (pin "1") (pintype "passive"))
      (node (ref "TP9") (pin "1") (pintype "passive"))
    )
    (net (code "46") (name "CD") (class "Default")
      (node (ref "D2") (pin "2") (pinfunction "A_2") (pintype "passive"))
    )
    (net (code "47") (name "CFETOFF") (class "Default")
      (node (ref "J5") (pin "3") (pinfunction "3_3") (pintype "passive"))
      (node (ref "U1") (pin "29") (pinfunction "CFETOFF_29") (pintype "bidirectional"))
    )
    (net (code "48") (name "CHG") (class "Default")
      (node (ref "U1") (pin "45") (pinfunction "CHG_45") (pintype "output"))
    )
    (net (code "49") (name "DSG") (class "Default")
      (node (ref "U1") (pin "43") (pinfunction "DSG_43") (pintype "output"))
    )
    (net (code "50") (name "FUSE") (class "Default")
      (node (ref "U1") (pin "38") (pinfunction "FUSE_38") (pintype "input"))
    )
    (net (code "51") (name "HDQ") (class "Default")
      (node (ref "U1") (pin "28") (pinfunction "HDQ_28") (pintype "bidirectional"))
    )
    (net (code "52") (name "LD") (class "Default")
      (node (ref "U1") (pin "41") (pinfunction "LD_41") (pintype "bidirectional"))
    )
    (net (code "53") (name "Net-(C71-Pad1)") (class "Default")
      (node (ref "C71") (pin "1") (pinfunction "1_1") (pintype "passive"))
      (node (ref "Q1") (pin "2") (pinfunction "C_2") (pintype "passive"))
      (node (ref "Q1") (pin "4") (pinfunction "C_4") (pintype "passive"))
      (node (ref "R10") (pin "1") (pinfunction "1_1") (pintype "passive"))
      (node (ref "R9") (pin "1") (pinfunction "1_1") (pintype "passive"))
    )
    (net (code "54") (name "Net-(D1-K)") (class "Default")
      (node (ref "D1") (pin "1") (pinfunction "K_1") (pintype "passive"))
      (node (ref "R1") (pin "2") (pinfunction "2_2") (pintype "passive"))
    )
    (net (code "55") (name "Net-(D2-K)") (class "Default")
      (node (ref "D2") (pin "1") (pinfunction "K_1") (pintype "passive"))
      (node (ref "R5") (pin "2") (pinfunction "2_2") (pintype "passive"))
      (node (ref "R6") (pin "2") (pinfunction "2_2") (pintype "passive"))
    )
    (net (code "56") (name "Net-(J2-Pad4)") (class "Default")
      (node (ref "J2") (pin "4") (pinfunction "4_4") (pintype "passive"))
      (node (ref "R15") (pin "2") (pinfunction "2_2") (pintype "passive"))
    )
    (net (code "57") (name "Net-(J6-Pad1)") (class "Default")
      (node (ref "J6") (pin "1") (pinfunction "1_1") (pintype "passive"))
      (node (ref "R25") (pin "2") (pinfunction "2_2") (pintype "passive"))
    )
    (net (code "58") (name "Net-(J6-Pad3)") (class "Default")
      (node (ref "J6") (pin "3") (pinfunction "3_3") (pintype "passive"))
      (node (ref "R26") (pin "2") (pinfunction "2_2") (pintype "passive"))
    )
    (net (code "59") (name "Net-(J7-Pad3)") (class "Default")
      (node (ref "J7") (pin "3") (pinfunction "3_3") (pintype "passive"))
      (node (ref "R29") (pin "2") (pinfunction "2_2") (pintype "passive"))
      (node (ref "S2") (pin "1") (pinfunction "1_1") (pintype "passive"))
      (node (ref "S2") (pin "2") (pinfunction "2_2") (pintype "passive"))
    )
    (net (code "60") (name "Net-(R5-Pad1)") (class "Default")
      (node (ref "R5") (pin "1") (pinfunction "1_1") (pintype "passive"))
      (node (ref "R9") (pin "2") (pinfunction "2_2") (pintype "passive"))
    )
    (net (code "61") (name "Net-(R10-Pad2)") (class "Default")
      (node (ref "R10") (pin "2") (pinfunction "2_2") (pintype "passive"))
      (node (ref "R6") (pin "1") (pinfunction "1_1") (pintype "passive"))
    )
    (net (code "62") (name "Net-(U1-BAT)") (class "Default")
      (node (ref "C1") (pin "1") (pinfunction "1_1") (pintype "passive"))
      (node (ref "C2") (pin "1") (pinfunction "1_1") (pintype "passive"))
      (node (ref "C3") (pin "1") (pinfunction "1_1") (pintype "passive"))
      (node (ref "R1") (pin "1") (pinfunction "1_1") (pintype "passive"))
      (node (ref "TP2") (pin "1") (pintype "passive"))
      (node (ref "U1") (pin "47") (pinfunction "BAT_47") (pintype "power_in"))
    )
    (net (code "63") (name "Net-(U1-CP1)") (class "Default")
      (node (ref "C3") (pin "2") (pinfunction "2_2") (pintype "passive"))
      (node (ref "TP3") (pin "1") (pintype "passive"))
      (node (ref "U1") (pin "46") (pinfunction "CP1_46") (pintype "bidirectional"))
    )
    (net (code "64") (name "Net-(U1-REG18)") (class "Default")
      (node (ref "C25") (pin "2") (pinfunction "2_2") (pintype "passive"))
      (node (ref "C26") (pin "1") (pinfunction "1_1") (pintype "passive"))
      (node (ref "TP10") (pin "1") (pintype "passive"))
      (node (ref "U1") (pin "24") (pinfunction "REG18_24") (pintype "power_in"))
    )
    (net (code "65") (name "Net-(U1-TS1)") (class "Default")
      (node (ref "RT1") (pin "1") (pinfunction "1_1") (pintype "passive"))
      (node (ref "TP7") (pin "1") (pintype "passive"))
      (node (ref "U1") (pin "21") (pinfunction "TS1_21") (pintype "bidirectional"))
    )
    (net (code "66") (name "Net-(U1-TS3)") (class "Default")
      (node (ref "RT2") (pin "1") (pinfunction "1_1") (pintype "passive"))
      (node (ref "TP8") (pin "1") (pintype "passive"))
      (node (ref "U1") (pin "23") (pinfunction "TS3_23") (pintype "bidirectional"))
    )
    (net (code "67") (name "PACK") (class "Default")
      (node (ref "U1") (pin "42") (pinfunction "PACK_42") (pintype "bidirectional"))
    )
    (net (code "68") (name "PCHG") (class "Default")
      (node (ref "U1") (pin "40") (pinfunction "PCHG_40") (pintype "output"))
    )
    (net (code "69") (name "PDSG") (class "Default")
      (node (ref "U1") (pin "39") (pinfunction "PDSG_39") (pintype "output"))
    )
    (net (code "70") (name "PGND") (class "Default")
      (node (ref "R28") (pin "1") (pinfunction "1_1") (pintype "passive"))
      (node (ref "R30") (pin "1") (pinfunction "1_1") (pintype "passive"))
    )
    (net (code "71") (name "REG1") (class "Default")
      (node (ref "C12") (pin "2") (pinfunction "2_2") (pintype "passive"))
      (node (ref "J2") (pin "3") (pinfunction "3_3") (pintype "passive"))
      (node (ref "R25") (pin "1") (pinfunction "1_1") (pintype "passive"))
      (node (ref "S1") (pin "3") (pinfunction "3_3") (pintype "passive"))
      (node (ref "S1") (pin "4") (pinfunction "4_4") (pintype "passive"))
      (node (ref "TP6") (pin "1") (pintype "passive"))
      (node (ref "U1") (pin "35") (pinfunction "REG1_35") (pintype "power_in"))
    )
    (net (code "72") (name "REG2") (class "Default")
      (node (ref "C15") (pin "2") (pinfunction "2_2") (pintype "passive"))
      (node (ref "J2") (pin "2") (pinfunction "2_2") (pintype "passive"))
      (node (ref "U1") (pin "34") (pinfunction "REG2_34") (pintype "power_in"))
    )
    (net (code "73") (name "SCL") (class "Default")
      (node (ref "U1") (pin "26") (pinfunction "SCL_26") (pintype "bidirectional"))
    )
    (net (code "74") (name "SDA") (class "Default")
      (node (ref "U1") (pin "27") (pinfunction "SDA_27") (pintype "bidirectional"))
    )
    (net (code "75") (name "VSS") (class "Default")
      (node (ref "C1") (pin "2") (pinfunction "2_2") (pintype "passive"))
      (node (ref "C12") (pin "1") (pinfunction "1_1") (pintype "passive"))
      (node (ref "C13") (pin "1") (pinfunction "1_1") (pintype "passive"))
      (node (ref "C15") (pin "1") (pinfunction "1_1") (pintype "passive"))
      (node (ref "C2") (pin "2") (pinfunction "2_2") (pintype "passive"))
      (node (ref "C20") (pin "2") (pinfunction "2_2") (pintype "passive"))
      (node (ref "C23") (pin "2") (pinfunction "2_2") (pintype "passive"))
      (node (ref "C24") (pin "2") (pinfunction "2_2") (pintype "passive"))
      (node (ref "C25") (pin "1") (pinfunction "1_1") (pintype "passive"))
      (node (ref "C26") (pin "2") (pinfunction "2_2") (pintype "passive"))
      (node (ref "C71") (pin "2") (pinfunction "2_2") (pintype "passive"))
      (node (ref "J2") (pin "1") (pinfunction "1_1") (pintype "passive"))
      (node (ref "J5") (pin "1") (pinfunction "1_1") (pintype "passive"))
      (node (ref "NT1") (pin "1") (pinfunction "1_1") (pintype "passive"))
      (node (ref "R20") (pin "2") (pinfunction "2_2") (pintype "passive"))
      (node (ref "R26") (pin "1") (pinfunction "1_1") (pintype "passive"))
      (node (ref "R29") (pin "1") (pinfunction "1_1") (pintype "passive"))
      (node (ref "RT1") (pin "2") (pinfunction "2_2") (pintype "passive"))
      (node (ref "RT2") (pin "2") (pinfunction "2_2") (pintype "passive"))
      (node (ref "TP14") (pin "1") (pintype "passive"))
      (node (ref "TP15") (pin "1") (pintype "passive"))
      (node (ref "TP16") (pin "1") (pintype "passive"))
      (node (ref "TP17") (pin "1") (pintype "passive"))
      (node (ref "TP18") (pin "1") (pintype "passive"))
      (node (ref "U1") (pin "17") (pinfunction "VSS_17") (pintype "power_in"))
    )
    (net (code "76") (name "unconnected-(U1-NC-Pad19)") (class "Default")
      (node (ref "U1") (pin "19") (pinfunction "NC_19") (pintype "passive+no_connect"))
    )
    (net (code "77") (name "unconnected-(U1-NC-Pad44)") (class "Default")
      (node (ref "U1") (pin "44") (pinfunction "NC_44") (pintype "passive+no_connect"))
    )
  )
)
